# HEADERS_JCTL.net
KiCad netlist of a schematic drawn in Altium Designer
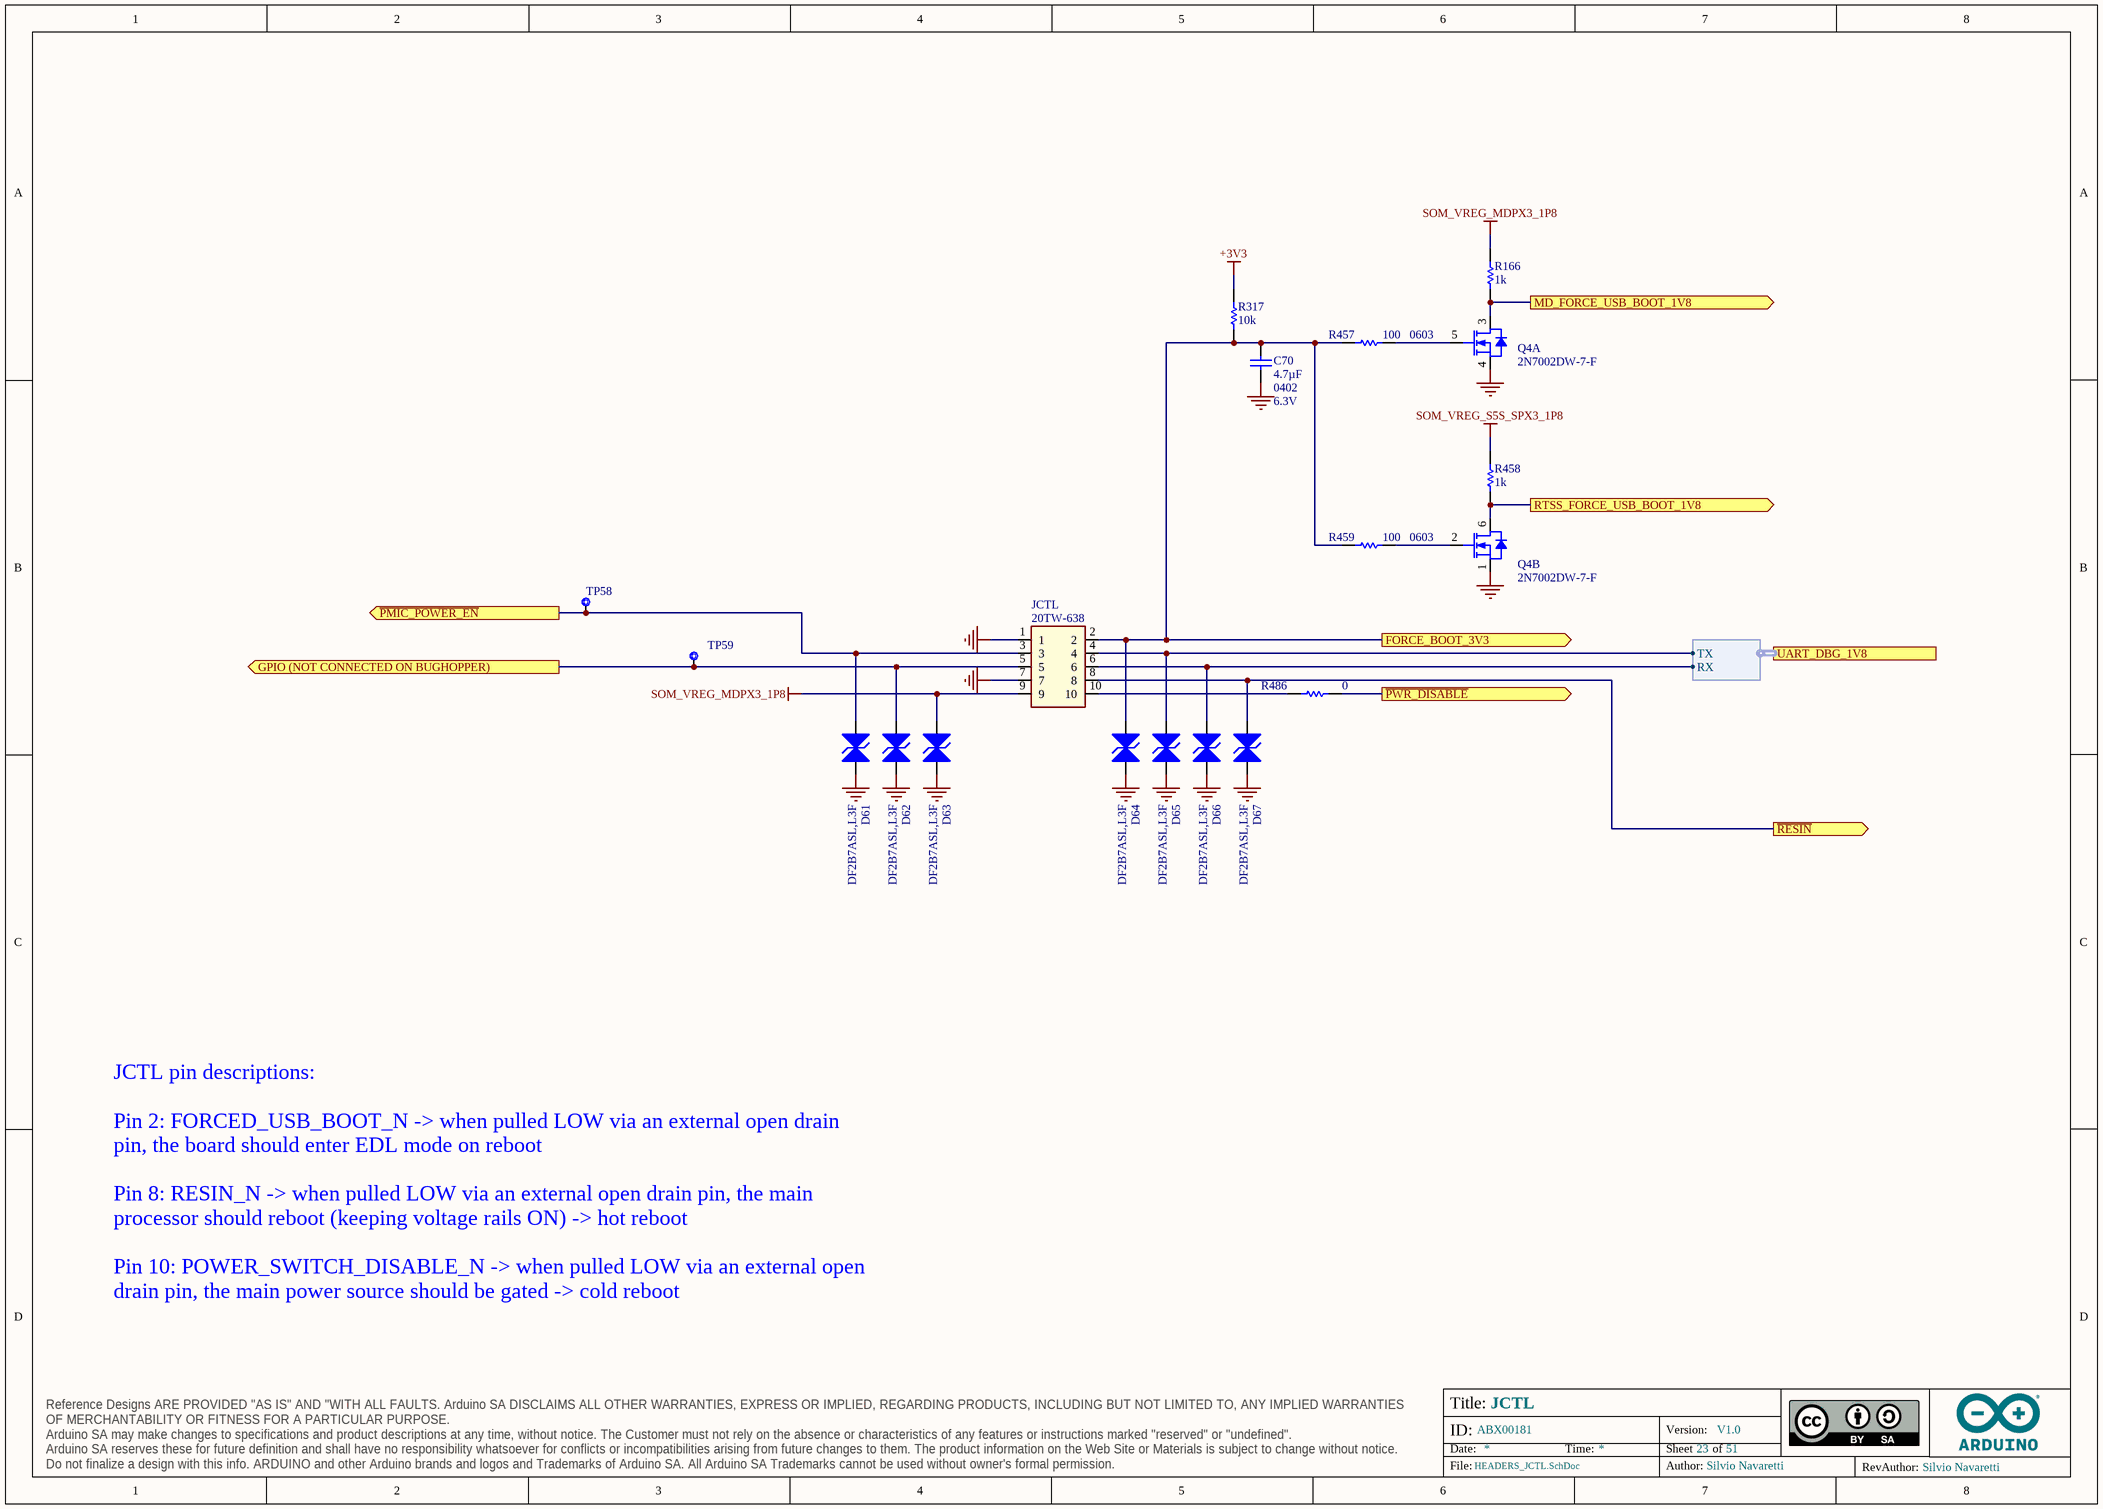
[diagram p0: HEADERS_JCTL.SchDoc]

(export (version "E")
  (design (tool "Eeschema 10.0.6"))
  (components
    (comp (ref "C70")
      (value "4.7µF")
      (footprint "CAP-0402")
      (description "CAP CHIP 0402 4.7uF 20% 6V3 X5R")
      (fields
        (field (name "MANUFACTURER") "Hottech")
        (field (name "PART NUMBER") "C1005A475M6R3NT")
        (field (name "CASE CODE (IMPERIAL)") "0402")
        (field (name "VOLTAGE") "6.3V")
      )
      (libsource (lib "Clean") (part "CAP"))
    )
    (comp (ref "D61")
      (value "DF2B7ASL,L3F")
      (footprint "DF2B7ASL,L3F")
      (description "TVS BIDIRECTIONAL SMD Vr 5.5V, Vbr min 5.8V, 0.62x0.32mm")
      (fields (field (name "MANUFACTURER") "TOSHIBA"))
      (libsource (lib "Clean") (part "Diode TVS"))
    )
    (comp (ref "D62")
      (value "DF2B7ASL,L3F")
      (footprint "DF2B7ASL,L3F")
      (description "TVS BIDIRECTIONAL SMD Vr 5.5V, Vbr min 5.8V, 0.62x0.32mm")
      (fields (field (name "MANUFACTURER") "TOSHIBA"))
      (libsource (lib "Clean") (part "Diode TVS"))
    )
    (comp (ref "D63")
      (value "DF2B7ASL,L3F")
      (footprint "DF2B7ASL,L3F")
      (description "TVS BIDIRECTIONAL SMD Vr 5.5V, Vbr min 5.8V, 0.62x0.32mm")
      (fields (field (name "MANUFACTURER") "TOSHIBA"))
      (libsource (lib "Clean") (part "Diode TVS"))
    )
    (comp (ref "D64")
      (value "DF2B7ASL,L3F")
      (footprint "DF2B7ASL,L3F")
      (description "TVS BIDIRECTIONAL SMD Vr 5.5V, Vbr min 5.8V, 0.62x0.32mm")
      (fields (field (name "MANUFACTURER") "TOSHIBA"))
      (libsource (lib "Clean") (part "Diode TVS"))
    )
    (comp (ref "D65")
      (value "DF2B7ASL,L3F")
      (footprint "DF2B7ASL,L3F")
      (description "TVS BIDIRECTIONAL SMD Vr 5.5V, Vbr min 5.8V, 0.62x0.32mm")
      (fields (field (name "MANUFACTURER") "TOSHIBA"))
      (libsource (lib "Clean") (part "Diode TVS"))
    )
    (comp (ref "D66")
      (value "DF2B7ASL,L3F")
      (footprint "DF2B7ASL,L3F")
      (description "TVS BIDIRECTIONAL SMD Vr 5.5V, Vbr min 5.8V, 0.62x0.32mm")
      (fields (field (name "MANUFACTURER") "TOSHIBA"))
      (libsource (lib "Clean") (part "Diode TVS"))
    )
    (comp (ref "D67")
      (value "DF2B7ASL,L3F")
      (footprint "DF2B7ASL,L3F")
      (description "TVS BIDIRECTIONAL SMD Vr 5.5V, Vbr min 5.8V, 0.62x0.32mm")
      (fields (field (name "MANUFACTURER") "TOSHIBA"))
      (libsource (lib "Clean") (part "Diode TVS"))
    )
    (comp (ref "JCTL")
      (value "20TW-638")
      (footprint "20TW-638")
      (description "CONN HEADER MALE 10POS 2x5 2.54mm SMD")
      (fields (field (name "MANUFACTURER") "4UCONN"))
      (libsource (lib "Clean") (part "Copy of 95278-101-10LF"))
    )
    (comp (ref "Q4")
      (value "2N7002DW-7-F")
      (footprint "SOT363")
      (description "MOSFET 2N-CH 60V 0.32A SOT363")
      (fields (field (name "MANUFACTURER") "Diodes Inc.") (field (name "PART NUMBER") "2N7002DW-7-F"))
      (libsource (lib "Clean") (part "2N7002DW-7-F"))
    )
    (comp (ref "R166")
      (value "1k")
      (footprint "RES-0201")
      (description "RES CHIP 0201 1k 1% 1/20W")
      (fields (field (name "POWER") "50mW") (field (name "TOLERANCE") "1%"))
      (libsource (lib "Clean") (part "RES"))
    )
    (comp (ref "R317")
      (value "10k")
      (footprint "RES-0201")
      (description "RES CHIP 0201 10k 1% 1/20W")
      (fields (field (name "POWER") "50mW") (field (name "TOLERANCE") "1%"))
      (libsource (lib "Clean") (part "RES"))
    )
    (comp (ref "R457")
      (value "100")
      (footprint "RES-0603")
      (description "RES CHIP 0603 100R 1% 1/10W")
      (fields
        (field (name "PART NUMBER") "CRCW0603100RFKEAC")
        (field (name "TOLERANCE") "1%")
        (field (name "CASE CODE (IMPERIAL)") "0603")
      )
      (libsource (lib "Clean") (part "RES"))
    )
    (comp (ref "R458")
      (value "1k")
      (footprint "RES-0201")
      (description "RES CHIP 0201 1k 1% 1/20W")
      (fields (field (name "POWER") "50mW") (field (name "TOLERANCE") "1%"))
      (libsource (lib "Clean") (part "RES"))
    )
    (comp (ref "R459")
      (value "100")
      (footprint "RES-0603")
      (description "RES CHIP 0603 100R 1% 1/10W")
      (fields
        (field (name "PART NUMBER") "CRCW0603100RFKEAC")
        (field (name "TOLERANCE") "1%")
        (field (name "CASE CODE (IMPERIAL)") "0603")
      )
      (libsource (lib "Clean") (part "RES"))
    )
    (comp (ref "R486")
      (value "0")
      (footprint "RES-0201")
      (description "RES CHIP 0201 0R")
      (fields (field (name "MANUFACTURER") "Vishay") (field (name "PART NUMBER") "CRCW02010000Z0ED"))
      (libsource (lib "Clean") (part "RES"))
    )
    (comp (ref "TP58")
      (value "Test point 1.00mm")
      (footprint "TP-1.00MM")
      (fields (field (name "PART NUMBER") "This is not a component"))
      (libsource (lib "Clean") (part "TESTPOINT"))
    )
    (comp (ref "TP59")
      (value "Test point 1.00mm")
      (footprint "TP-1.00MM")
      (fields (field (name "PART NUMBER") "This is not a component"))
      (libsource (lib "Clean") (part "TESTPOINT"))
    )
  )
  (nets
    (net (code "2") (name "+3V3") (class "Default")
      (node (ref "R317") (pin "2") (pinfunction "2_2") (pintype "passive"))
    )
    (net (code "3") (name "/FORCE_BOOT_3V3") (class "Default")
      (node (ref "C70") (pin "1") (pinfunction "1_1") (pintype "passive"))
      (node (ref "D64") (pin "2") (pinfunction "A2_2") (pintype "passive"))
      (node (ref "JCTL") (pin "2") (pinfunction "2_2") (pintype "passive"))
      (node (ref "R317") (pin "1") (pinfunction "1_1") (pintype "passive"))
      (node (ref "R457") (pin "2") (pinfunction "2_2") (pintype "passive"))
      (node (ref "R459") (pin "2") (pinfunction "2_2") (pintype "passive"))
    )
    (net (code "4") (name "/GPIO (NOT CONNECTED ON BUGHOPPER)") (class "Default")
      (node (ref "D62") (pin "2") (pinfunction "A2_2") (pintype "passive"))
      (node (ref "JCTL") (pin "5") (pinfunction "5_5") (pintype "passive"))
      (node (ref "TP59") (pin "X") (pinfunction "X_X") (pintype "passive"))
    )
    (net (code "5") (name "/MD_FORCE_USB_BOOT_1V8") (class "Default")
      (node (ref "Q4") (pin "3") (pinfunction "D_3") (pintype "passive"))
      (node (ref "R166") (pin "2") (pinfunction "2_2") (pintype "passive"))
    )
    (net (code "6") (name "/RTSS_FORCE_USB_BOOT_1V8") (class "Default")
      (node (ref "Q4") (pin "6") (pinfunction "D_6") (pintype "passive"))
      (node (ref "R458") (pin "2") (pinfunction "2_2") (pintype "passive"))
    )
    (net (code "8") (name "/~{PMIC_POWER_EN}") (class "Default")
      (node (ref "D61") (pin "2") (pinfunction "A2_2") (pintype "passive"))
      (node (ref "JCTL") (pin "3") (pinfunction "3_3") (pintype "passive"))
      (node (ref "TP58") (pin "X") (pinfunction "X_X") (pintype "passive"))
    )
    (net (code "9") (name "/~{PWR_DISABLE}") (class "Default")
      (node (ref "R486") (pin "1") (pinfunction "1_1") (pintype "passive"))
    )
    (net (code "10") (name "/~{RESIN}") (class "Default")
      (node (ref "D67") (pin "2") (pinfunction "A2_2") (pintype "passive"))
      (node (ref "JCTL") (pin "8") (pinfunction "8_8") (pintype "passive"))
    )
    (net (code "11") (name "GND") (class "Default")
      (node (ref "C70") (pin "2") (pinfunction "2_2") (pintype "passive"))
      (node (ref "D61") (pin "1") (pinfunction "A1_1") (pintype "passive"))
      (node (ref "D62") (pin "1") (pinfunction "A1_1") (pintype "passive"))
      (node (ref "D63") (pin "1") (pinfunction "A1_1") (pintype "passive"))
      (node (ref "D64") (pin "1") (pinfunction "A1_1") (pintype "passive"))
      (node (ref "D65") (pin "1") (pinfunction "A1_1") (pintype "passive"))
      (node (ref "D66") (pin "1") (pinfunction "A1_1") (pintype "passive"))
      (node (ref "D67") (pin "1") (pinfunction "A1_1") (pintype "passive"))
      (node (ref "JCTL") (pin "1") (pinfunction "1_1") (pintype "passive"))
      (node (ref "JCTL") (pin "7") (pinfunction "7_7") (pintype "passive"))
      (node (ref "Q4") (pin "1") (pinfunction "S_1") (pintype "passive"))
      (node (ref "Q4") (pin "4") (pinfunction "S_4") (pintype "passive"))
    )
    (net (code "12") (name "Net-(D65-A2)") (class "Default")
      (node (ref "D65") (pin "2") (pinfunction "A2_2") (pintype "passive"))
      (node (ref "JCTL") (pin "4") (pinfunction "4_4") (pintype "passive"))
    )
    (net (code "13") (name "Net-(D66-A2)") (class "Default")
      (node (ref "D66") (pin "2") (pinfunction "A2_2") (pintype "passive"))
      (node (ref "JCTL") (pin "6") (pinfunction "6_6") (pintype "passive"))
    )
    (net (code "14") (name "Net-(JCTL-Pad10)") (class "Default")
      (node (ref "JCTL") (pin "10") (pinfunction "10_10") (pintype "passive"))
      (node (ref "R486") (pin "2") (pinfunction "2_2") (pintype "passive"))
    )
    (net (code "15") (name "Net-(Q4A-G)") (class "Default")
      (node (ref "Q4") (pin "5") (pinfunction "G_5") (pintype "passive"))
      (node (ref "R457") (pin "1") (pinfunction "1_1") (pintype "passive"))
    )
    (net (code "16") (name "Net-(Q4B-G)") (class "Default")
      (node (ref "Q4") (pin "2") (pinfunction "G_2") (pintype "passive"))
      (node (ref "R459") (pin "1") (pinfunction "1_1") (pintype "passive"))
    )
    (net (code "17") (name "SOM_VREG_MDPX3_1P8") (class "Default")
      (node (ref "D63") (pin "2") (pinfunction "A2_2") (pintype "passive"))
      (node (ref "JCTL") (pin "9") (pinfunction "9_9") (pintype "passive"))
      (node (ref "R166") (pin "1") (pinfunction "1_1") (pintype "passive"))
    )
    (net (code "18") (name "SOM_VREG_S5S_SPX3_1P8") (class "Default")
      (node (ref "R458") (pin "1") (pinfunction "1_1") (pintype "passive"))
    )
  )
)
